# busfahrer_pi.net
KiCad netlist of a schematic drawn in EAGLE
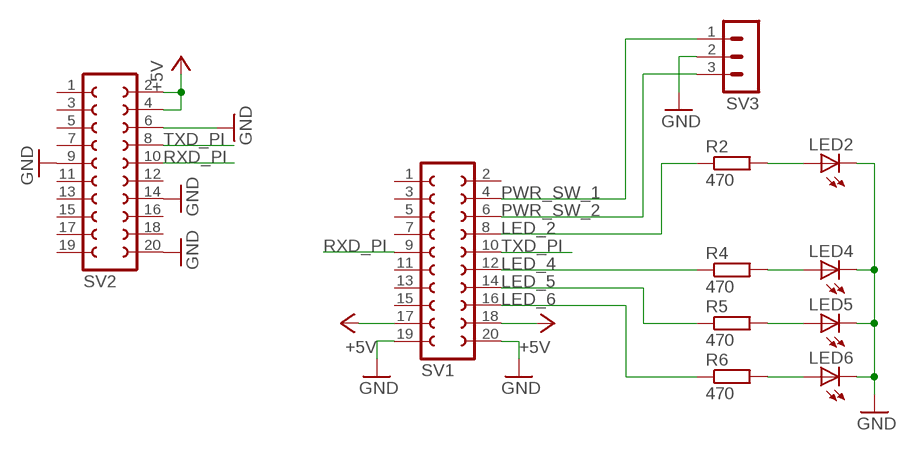
[diagram p0: schematic, sheet 1]

(export (version "E")
  (design (tool "Eeschema 10.0.6"))
  (components
    (comp (ref "LED2")
      (value "LEDCHIPLED_0805")
      (footprint "eagle-import:CHIPLED_0805")
      (libsource (lib "eagle-import") (part "LEDCHIPLED_0805"))
    )
    (comp (ref "LED4")
      (value "LEDCHIPLED_0805")
      (footprint "eagle-import:CHIPLED_0805")
      (libsource (lib "eagle-import") (part "LEDCHIPLED_0805"))
    )
    (comp (ref "LED5")
      (value "LEDCHIPLED_0805")
      (footprint "eagle-import:CHIPLED_0805")
      (libsource (lib "eagle-import") (part "LEDCHIPLED_0805"))
    )
    (comp (ref "LED6")
      (value "LEDCHIPLED_0805")
      (footprint "eagle-import:CHIPLED_0805")
      (libsource (lib "eagle-import") (part "LEDCHIPLED_0805"))
    )
    (comp (ref "R2")
      (value "470")
      (footprint "eagle-import:R0805")
      (libsource (lib "eagle-import") (part "R-EU_R0805"))
    )
    (comp (ref "R4")
      (value "470")
      (footprint "eagle-import:R0805")
      (libsource (lib "eagle-import") (part "R-EU_R0805"))
    )
    (comp (ref "R5")
      (value "470")
      (footprint "eagle-import:R0805")
      (libsource (lib "eagle-import") (part "R-EU_R0805"))
    )
    (comp (ref "R6")
      (value "470")
      (footprint "eagle-import:R0805")
      (libsource (lib "eagle-import") (part "R-EU_R0805"))
    )
    (comp (ref "SV1")
      (value "FE10-2")
      (footprint "eagle-import:FE10-2")
      (libsource (lib "eagle-import") (part "FE10-2"))
    )
    (comp (ref "SV2")
      (value "FE10-2")
      (footprint "eagle-import:FE10-2")
      (fields (field (name "OC_FARNELL") "unknown") (field (name "OC_NEWARK") "unknown"))
      (libsource (lib "eagle-import") (part "FE10-2"))
    )
    (comp (ref "SV3")
      (value "MA03-1")
      (footprint "eagle-import:MA03-1")
      (libsource (lib "eagle-import") (part "MA03-1"))
    )
  )
  (nets
    (net (code "1") (name "+5V") (class "Default")
      (node (ref "SV1") (pin "17") (pinfunction "17_17") (pintype "passive"))
      (node (ref "SV1") (pin "18") (pinfunction "18_18") (pintype "passive"))
      (node (ref "SV2") (pin "2") (pinfunction "2_2") (pintype "passive"))
      (node (ref "SV2") (pin "4") (pinfunction "4_4") (pintype "passive"))
    )
    (net (code "2") (name "/LED_2") (class "Default")
      (node (ref "R2") (pin "1") (pinfunction "1_1") (pintype "passive"))
      (node (ref "SV1") (pin "8") (pinfunction "8_8") (pintype "passive"))
    )
    (net (code "3") (name "/LED_4") (class "Default")
      (node (ref "R4") (pin "1") (pinfunction "1_1") (pintype "passive"))
      (node (ref "SV1") (pin "12") (pinfunction "12_12") (pintype "passive"))
    )
    (net (code "4") (name "/LED_5") (class "Default")
      (node (ref "R5") (pin "1") (pinfunction "1_1") (pintype "passive"))
      (node (ref "SV1") (pin "14") (pinfunction "14_14") (pintype "passive"))
    )
    (net (code "5") (name "/LED_6") (class "Default")
      (node (ref "R6") (pin "1") (pinfunction "1_1") (pintype "passive"))
      (node (ref "SV1") (pin "16") (pinfunction "16_16") (pintype "passive"))
    )
    (net (code "6") (name "/PWR_SW_1") (class "Default")
      (node (ref "SV1") (pin "4") (pinfunction "4_4") (pintype "passive"))
      (node (ref "SV3") (pin "1") (pinfunction "1_1") (pintype "passive"))
    )
    (net (code "7") (name "/PWR_SW_2") (class "Default")
      (node (ref "SV1") (pin "6") (pinfunction "6_6") (pintype "passive"))
      (node (ref "SV3") (pin "3") (pinfunction "3_3") (pintype "passive"))
    )
    (net (code "8") (name "/RXD_PI") (class "Default")
      (node (ref "SV1") (pin "9") (pinfunction "9_9") (pintype "passive"))
      (node (ref "SV2") (pin "10") (pinfunction "10_10") (pintype "passive"))
    )
    (net (code "9") (name "/TXD_PI") (class "Default")
      (node (ref "SV1") (pin "10") (pinfunction "10_10") (pintype "passive"))
      (node (ref "SV2") (pin "8") (pinfunction "8_8") (pintype "passive"))
    )
    (net (code "10") (name "GND") (class "Default")
      (node (ref "LED2") (pin "C") (pinfunction "C_C") (pintype "passive"))
      (node (ref "LED4") (pin "C") (pinfunction "C_C") (pintype "passive"))
      (node (ref "LED5") (pin "C") (pinfunction "C_C") (pintype "passive"))
      (node (ref "LED6") (pin "C") (pinfunction "C_C") (pintype "passive"))
      (node (ref "SV1") (pin "19") (pinfunction "19_19") (pintype "passive"))
      (node (ref "SV1") (pin "20") (pinfunction "20_20") (pintype "passive"))
      (node (ref "SV2") (pin "14") (pinfunction "14_14") (pintype "passive"))
      (node (ref "SV2") (pin "20") (pinfunction "20_20") (pintype "passive"))
      (node (ref "SV2") (pin "6") (pinfunction "6_6") (pintype "passive"))
      (node (ref "SV2") (pin "9") (pinfunction "9_9") (pintype "passive"))
      (node (ref "SV3") (pin "2") (pinfunction "2_2") (pintype "passive"))
    )
    (net (code "11") (name "Net-(LED2-PadA)") (class "Default")
      (node (ref "LED2") (pin "A") (pinfunction "A_A") (pintype "passive"))
      (node (ref "R2") (pin "2") (pinfunction "2_2") (pintype "passive"))
    )
    (net (code "12") (name "Net-(LED4-PadA)") (class "Default")
      (node (ref "LED4") (pin "A") (pinfunction "A_A") (pintype "passive"))
      (node (ref "R4") (pin "2") (pinfunction "2_2") (pintype "passive"))
    )
    (net (code "13") (name "Net-(LED5-PadA)") (class "Default")
      (node (ref "LED5") (pin "A") (pinfunction "A_A") (pintype "passive"))
      (node (ref "R5") (pin "2") (pinfunction "2_2") (pintype "passive"))
    )
    (net (code "14") (name "Net-(LED6-PadA)") (class "Default")
      (node (ref "LED6") (pin "A") (pinfunction "A_A") (pintype "passive"))
      (node (ref "R6") (pin "2") (pinfunction "2_2") (pintype "passive"))
    )
    (net (code "15") (name "unconnected-(SV1-Pad1)") (class "Default")
      (node (ref "SV1") (pin "1") (pinfunction "1_1") (pintype "passive"))
    )
    (net (code "16") (name "unconnected-(SV1-Pad2)") (class "Default")
      (node (ref "SV1") (pin "2") (pinfunction "2_2") (pintype "passive"))
    )
    (net (code "17") (name "unconnected-(SV1-Pad3)") (class "Default")
      (node (ref "SV1") (pin "3") (pinfunction "3_3") (pintype "passive"))
    )
    (net (code "18") (name "unconnected-(SV1-Pad5)") (class "Default")
      (node (ref "SV1") (pin "5") (pinfunction "5_5") (pintype "passive"))
    )
    (net (code "19") (name "unconnected-(SV1-Pad7)") (class "Default")
      (node (ref "SV1") (pin "7") (pinfunction "7_7") (pintype "passive"))
    )
    (net (code "20") (name "unconnected-(SV1-Pad11)") (class "Default")
      (node (ref "SV1") (pin "11") (pinfunction "11_11") (pintype "passive"))
    )
    (net (code "21") (name "unconnected-(SV1-Pad13)") (class "Default")
      (node (ref "SV1") (pin "13") (pinfunction "13_13") (pintype "passive"))
    )
    (net (code "22") (name "unconnected-(SV1-Pad15)") (class "Default")
      (node (ref "SV1") (pin "15") (pinfunction "15_15") (pintype "passive"))
    )
    (net (code "23") (name "unconnected-(SV2-Pad1)") (class "Default")
      (node (ref "SV2") (pin "1") (pinfunction "1_1") (pintype "passive"))
    )
    (net (code "24") (name "unconnected-(SV2-Pad3)") (class "Default")
      (node (ref "SV2") (pin "3") (pinfunction "3_3") (pintype "passive"))
    )
    (net (code "25") (name "unconnected-(SV2-Pad5)") (class "Default")
      (node (ref "SV2") (pin "5") (pinfunction "5_5") (pintype "passive"))
    )
    (net (code "26") (name "unconnected-(SV2-Pad7)") (class "Default")
      (node (ref "SV2") (pin "7") (pinfunction "7_7") (pintype "passive"))
    )
    (net (code "27") (name "unconnected-(SV2-Pad11)") (class "Default")
      (node (ref "SV2") (pin "11") (pinfunction "11_11") (pintype "passive"))
    )
    (net (code "28") (name "unconnected-(SV2-Pad12)") (class "Default")
      (node (ref "SV2") (pin "12") (pinfunction "12_12") (pintype "passive"))
    )
    (net (code "29") (name "unconnected-(SV2-Pad13)") (class "Default")
      (node (ref "SV2") (pin "13") (pinfunction "13_13") (pintype "passive"))
    )
    (net (code "30") (name "unconnected-(SV2-Pad15)") (class "Default")
      (node (ref "SV2") (pin "15") (pinfunction "15_15") (pintype "passive"))
    )
    (net (code "31") (name "unconnected-(SV2-Pad16)") (class "Default")
      (node (ref "SV2") (pin "16") (pinfunction "16_16") (pintype "passive"))
    )
    (net (code "32") (name "unconnected-(SV2-Pad17)") (class "Default")
      (node (ref "SV2") (pin "17") (pinfunction "17_17") (pintype "passive"))
    )
    (net (code "33") (name "unconnected-(SV2-Pad18)") (class "Default")
      (node (ref "SV2") (pin "18") (pinfunction "18_18") (pintype "passive"))
    )
    (net (code "34") (name "unconnected-(SV2-Pad19)") (class "Default")
      (node (ref "SV2") (pin "19") (pinfunction "19_19") (pintype "passive"))
    )
  )
)
